# anaMoCo.net
KiCad netlist of a schematic drawn in EAGLE
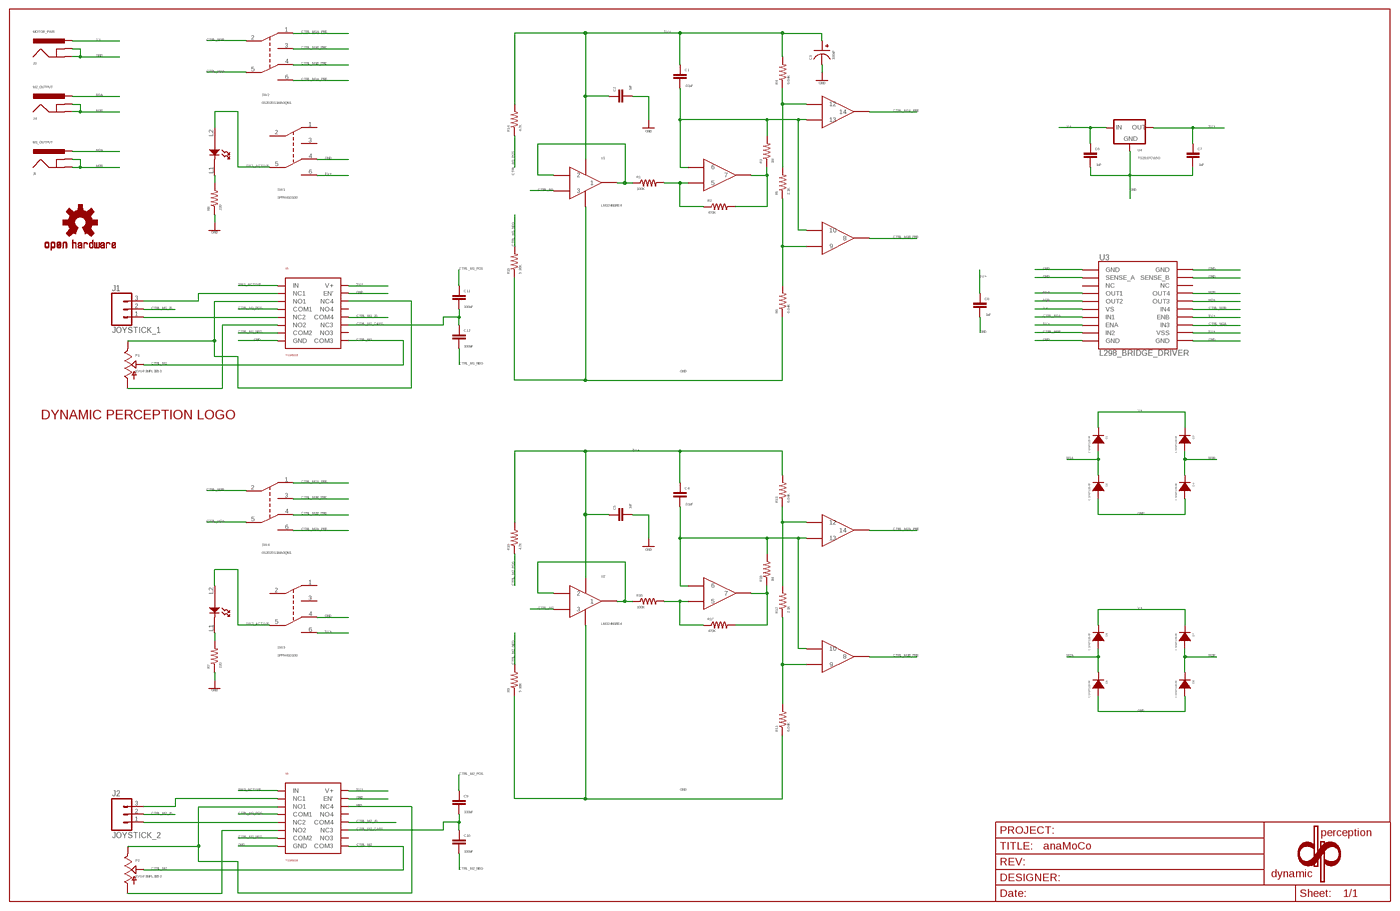
[diagram p0: schematic, sheet 1, overview]
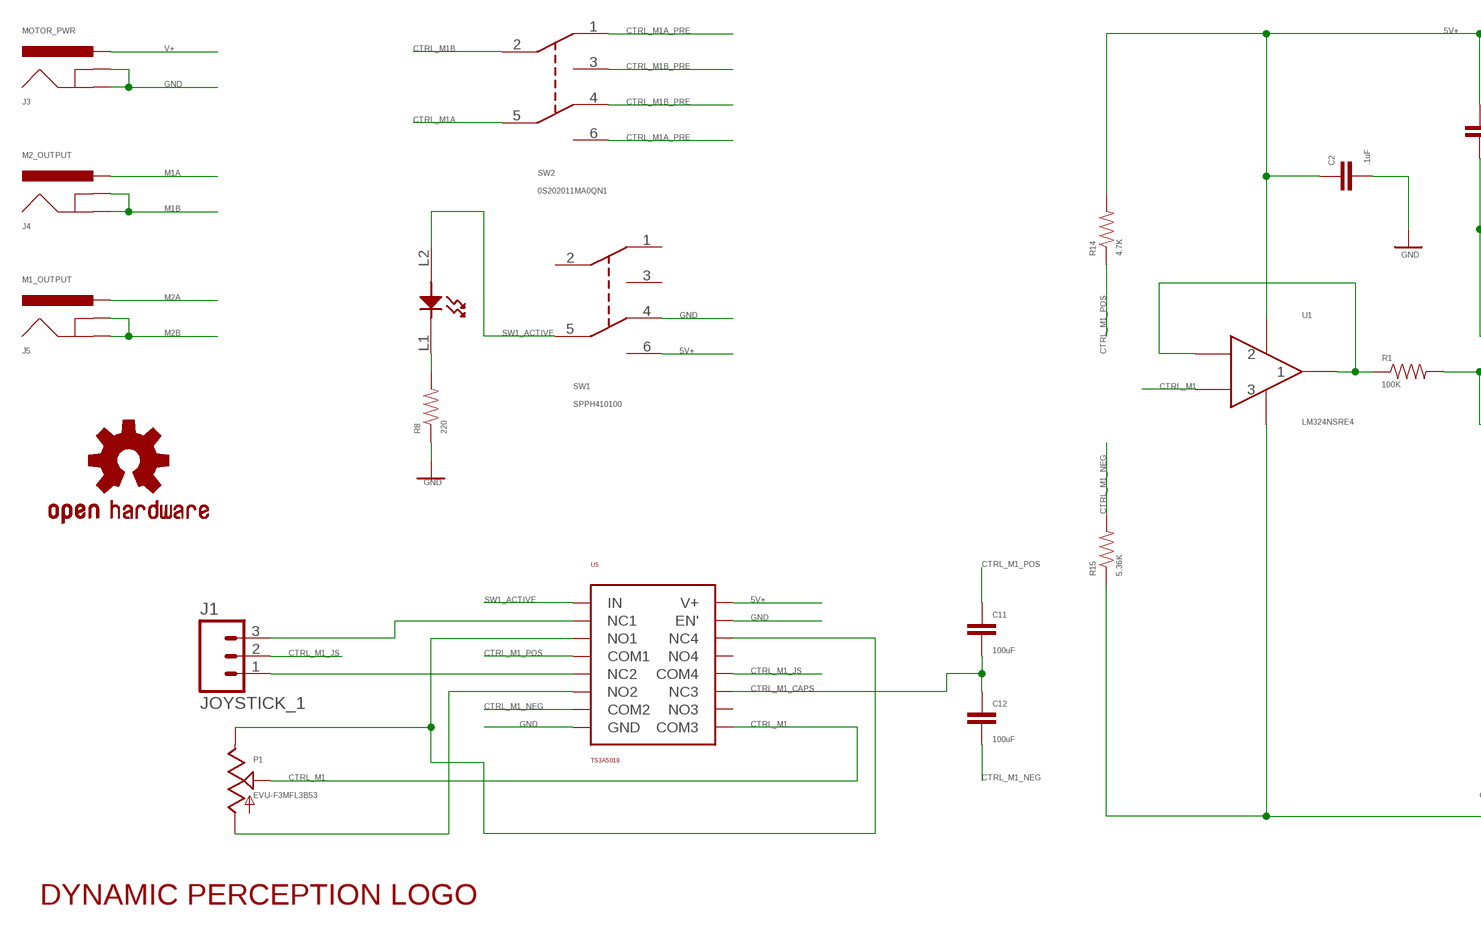
[diagram p1: schematic, sheet 1, part 1 of 4]
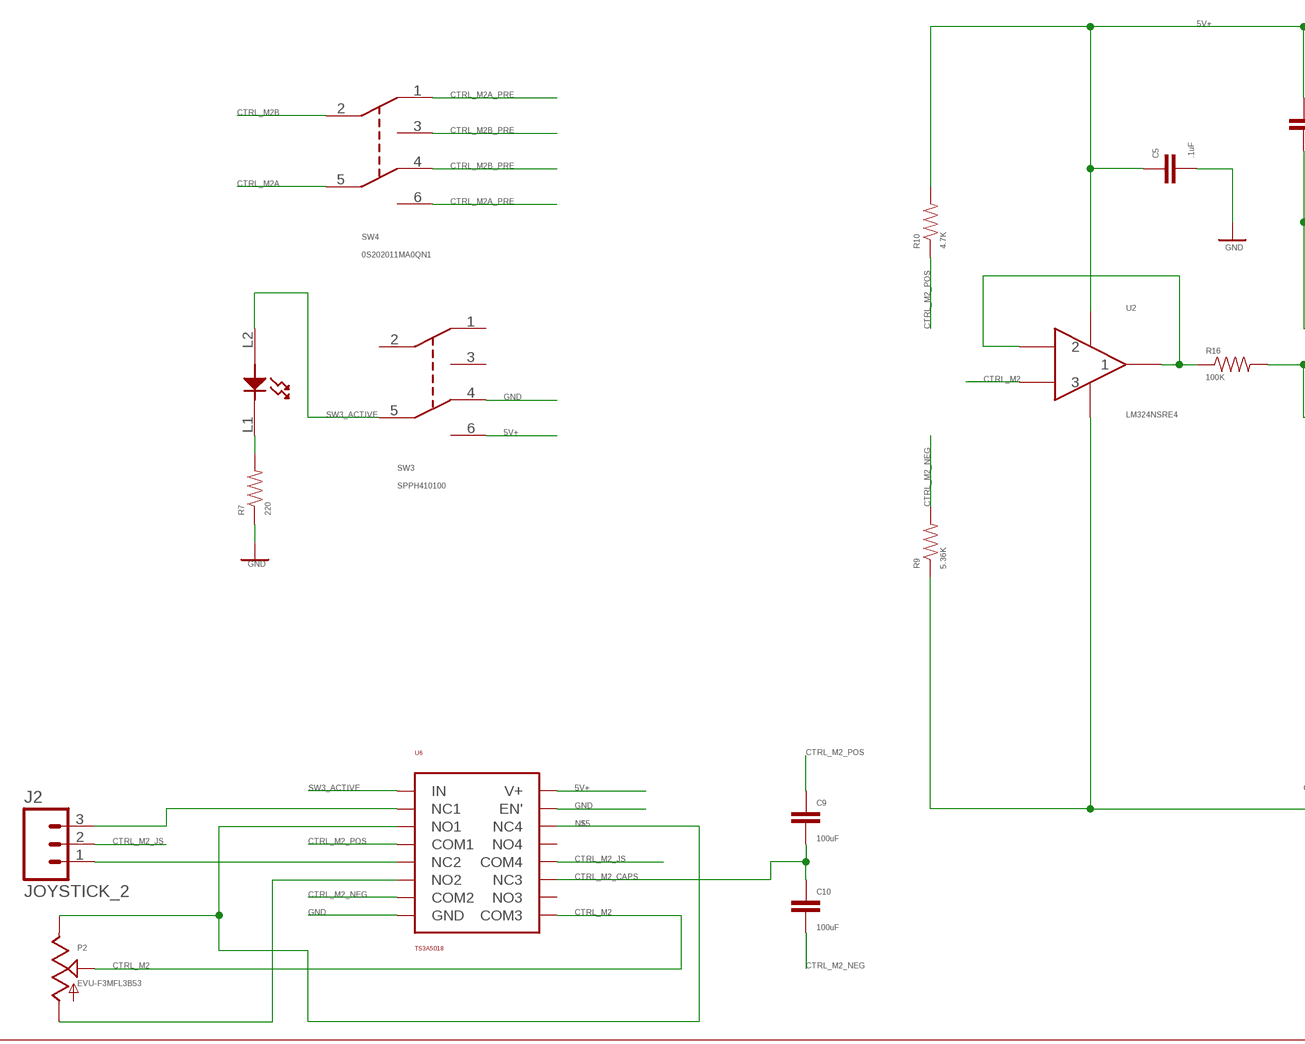
[diagram p2: schematic, sheet 1, part 2 of 4]
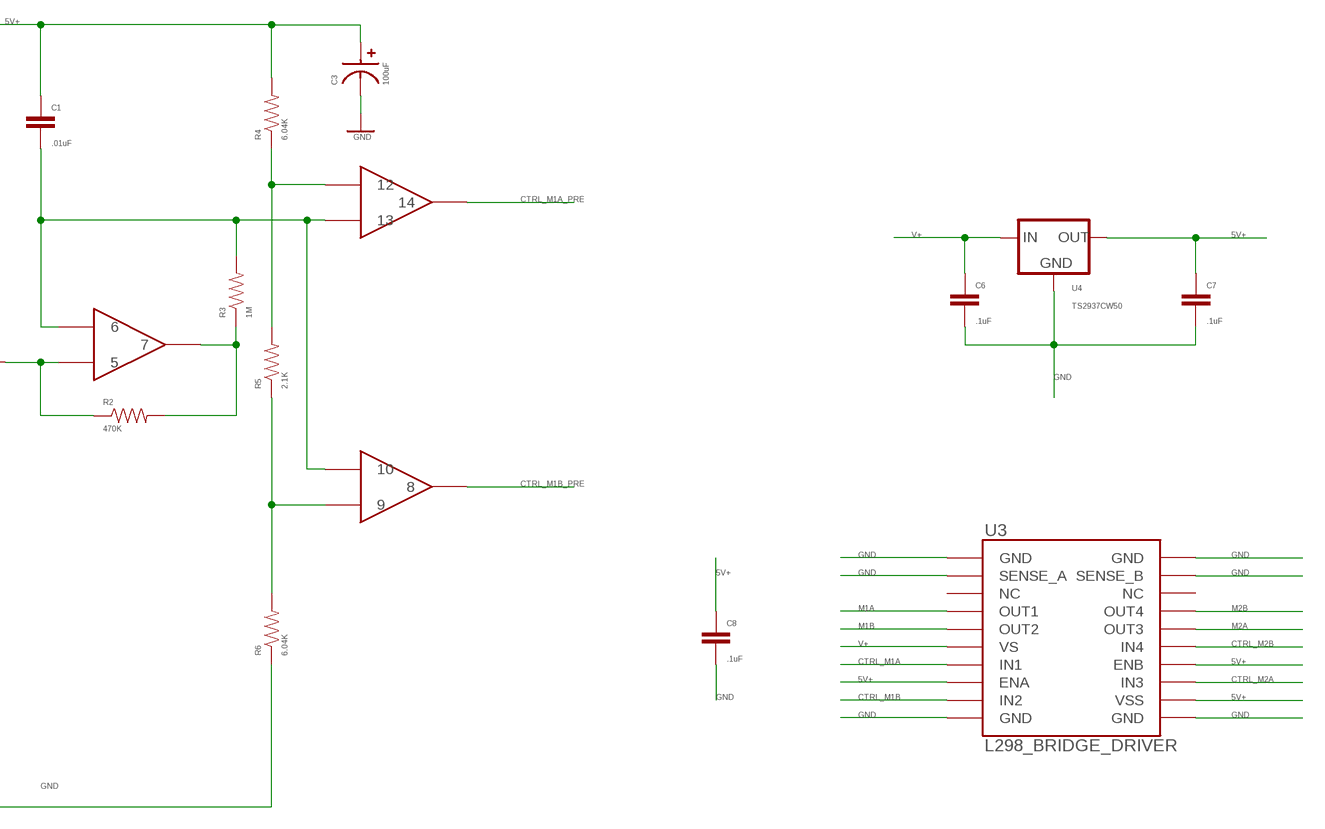
[diagram p3: schematic, sheet 1, part 3 of 4]
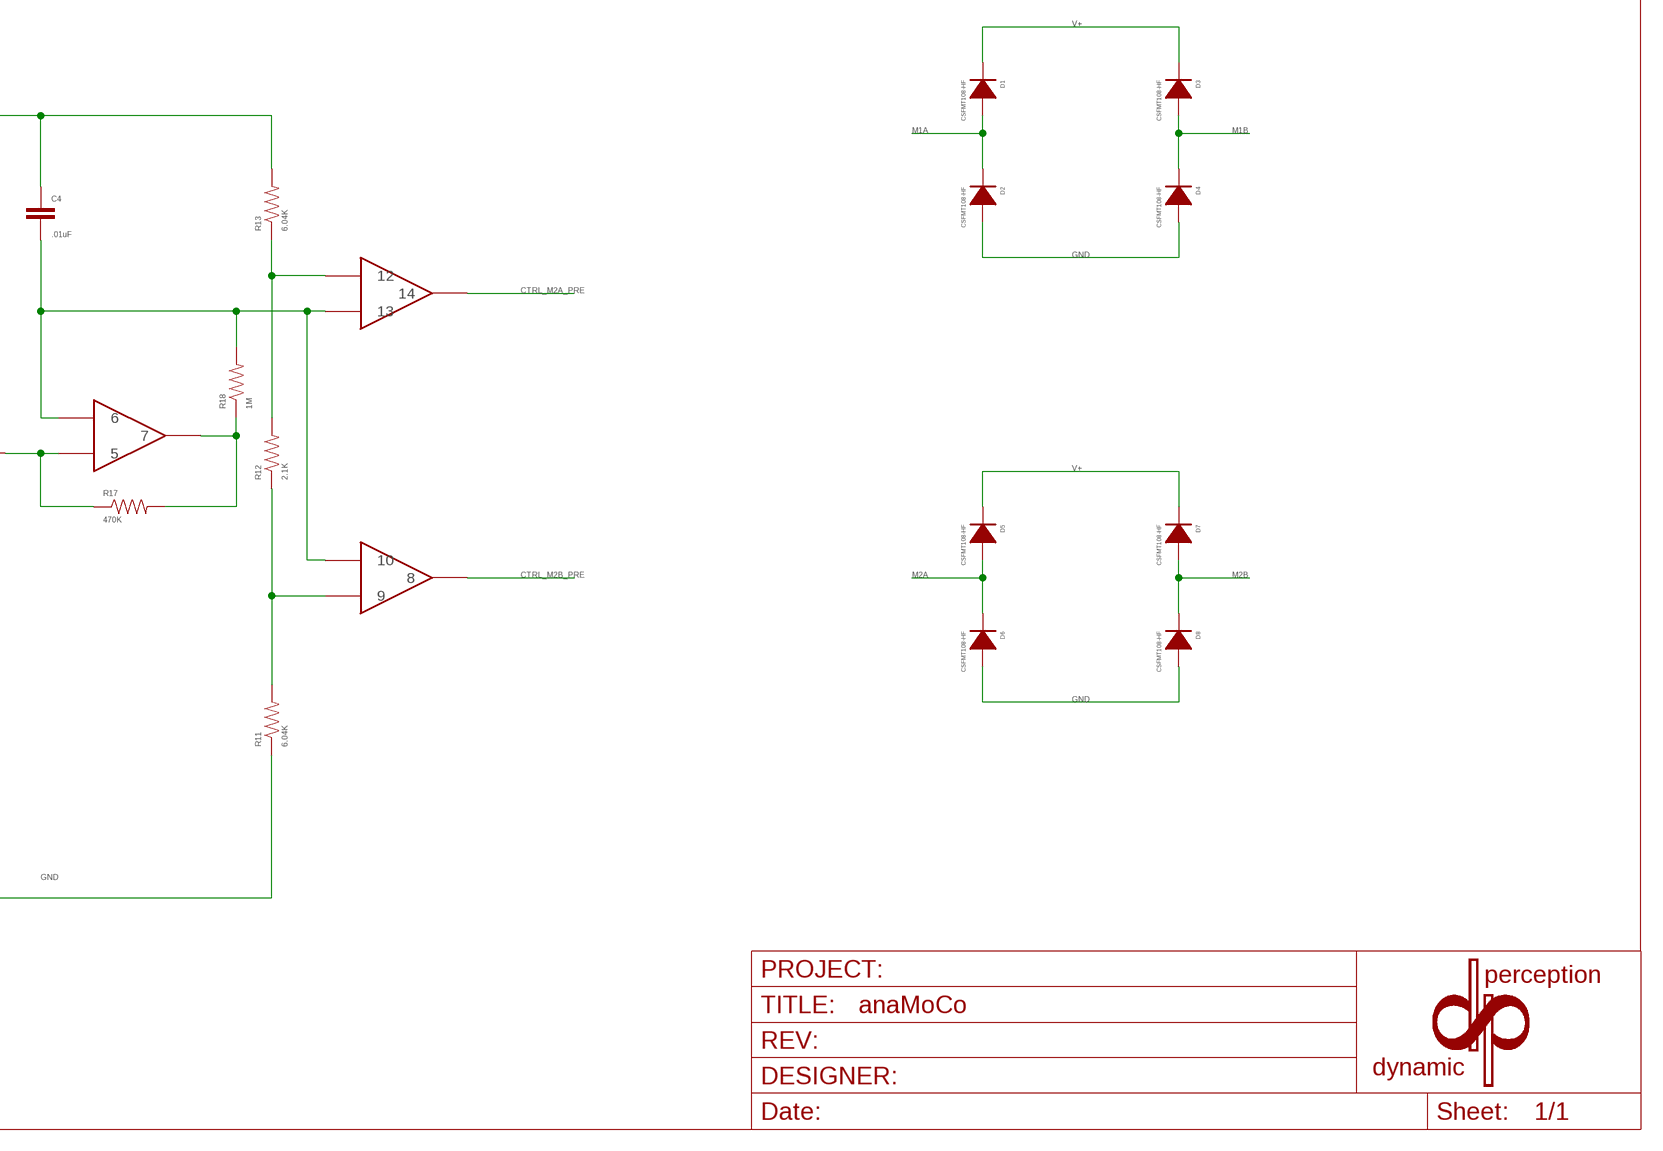
[diagram p4: schematic, sheet 1, part 4 of 4]

(export (version "E")
  (design (tool "Eeschema 10.0.6"))
  (components
    (comp (ref "C1")
      (value ".01uF")
      (footprint "eagle-import:0402_CAP")
      (libsource (lib "eagle-import") (part "CAP_NONPOL0402"))
    )
    (comp (ref "C2")
      (value ".1uF")
      (footprint "eagle-import:0402_CAP")
      (libsource (lib "eagle-import") (part "CAP_NONPOL0402"))
    )
    (comp (ref "C3")
      (value "100uF")
      (footprint "eagle-import:6.3MM_DIA_CAP_SMD")
      (libsource (lib "eagle-import") (part "CAP_POLARIZED6.3MM_SMD"))
    )
    (comp (ref "C4")
      (value ".01uF")
      (footprint "eagle-import:0402_CAP")
      (libsource (lib "eagle-import") (part "CAP_NONPOL0402"))
    )
    (comp (ref "C5")
      (value ".1uF")
      (footprint "eagle-import:0402_CAP")
      (libsource (lib "eagle-import") (part "CAP_NONPOL0402"))
    )
    (comp (ref "C6")
      (value ".1uF")
      (footprint "eagle-import:0402_CAP")
      (libsource (lib "eagle-import") (part "CAP_NONPOL0402"))
    )
    (comp (ref "C7")
      (value ".1uF")
      (footprint "eagle-import:0402_CAP")
      (libsource (lib "eagle-import") (part "CAP_NONPOL0402"))
    )
    (comp (ref "C8")
      (value ".1uF")
      (footprint "eagle-import:0402_CAP")
      (libsource (lib "eagle-import") (part "CAP_NONPOL0402"))
    )
    (comp (ref "C9")
      (value "100uF")
      (footprint "eagle-import:1206")
      (libsource (lib "eagle-import") (part "CAP1206"))
    )
    (comp (ref "C10")
      (value "100uF")
      (footprint "eagle-import:1206")
      (libsource (lib "eagle-import") (part "CAP1206"))
    )
    (comp (ref "C11")
      (value "100uF")
      (footprint "eagle-import:1206")
      (libsource (lib "eagle-import") (part "CAP1206"))
    )
    (comp (ref "C12")
      (value "100uF")
      (footprint "eagle-import:1206")
      (libsource (lib "eagle-import") (part "CAP1206"))
    )
    (comp (ref "D1")
      (value "CSFMT108-HF")
      (footprint "eagle-import:SOD-123")
      (libsource (lib "eagle-import") (part "1N4148WSOD-123"))
    )
    (comp (ref "D2")
      (value "CSFMT108-HF")
      (footprint "eagle-import:SOD-123")
      (libsource (lib "eagle-import") (part "1N4148WSOD-123"))
    )
    (comp (ref "D3")
      (value "CSFMT108-HF")
      (footprint "eagle-import:SOD-123")
      (libsource (lib "eagle-import") (part "1N4148WSOD-123"))
    )
    (comp (ref "D4")
      (value "CSFMT108-HF")
      (footprint "eagle-import:SOD-123")
      (libsource (lib "eagle-import") (part "1N4148WSOD-123"))
    )
    (comp (ref "D5")
      (value "CSFMT108-HF")
      (footprint "eagle-import:SOD-123")
      (libsource (lib "eagle-import") (part "1N4148WSOD-123"))
    )
    (comp (ref "D6")
      (value "CSFMT108-HF")
      (footprint "eagle-import:SOD-123")
      (libsource (lib "eagle-import") (part "1N4148WSOD-123"))
    )
    (comp (ref "D7")
      (value "CSFMT108-HF")
      (footprint "eagle-import:SOD-123")
      (libsource (lib "eagle-import") (part "1N4148WSOD-123"))
    )
    (comp (ref "D8")
      (value "CSFMT108-HF")
      (footprint "eagle-import:SOD-123")
      (libsource (lib "eagle-import") (part "1N4148WSOD-123"))
    )
    (comp (ref "J1")
      (value "JOYSTICK_1")
      (footprint "eagle-import:MOLEX-1X3")
      (libsource (lib "eagle-import") (part "M03POLAR"))
    )
    (comp (ref "J2")
      (value "JOYSTICK_2")
      (footprint "eagle-import:MOLEX-1X3")
      (libsource (lib "eagle-import") (part "M03POLAR"))
    )
    (comp (ref "J3")
      (value "MOTOR_PWR")
      (footprint "eagle-import:POWER_JACK_PTH")
      (libsource (lib "eagle-import") (part "POWER_JACKPTH"))
    )
    (comp (ref "J4")
      (value "M2_OUTPUT")
      (footprint "eagle-import:POWER_JACK_PTH")
      (libsource (lib "eagle-import") (part "POWER_JACKPTH"))
    )
    (comp (ref "J5")
      (value "M1_OUTPUT")
      (footprint "eagle-import:POWER_JACK_PTH")
      (libsource (lib "eagle-import") (part "POWER_JACKPTH"))
    )
    (comp (ref "LOGO1")
      (value "DP_LOGOLARGE")
      (footprint "eagle-import:DP_LOGO_LARGE")
      (libsource (lib "eagle-import") (part "DP_LOGOLARGE"))
    )
    (comp (ref "P1")
      (value "EVU-F3MFL3B53")
      (footprint "eagle-import:PTV09A-4_POT")
      (libsource (lib "eagle-import") (part "POTENTIOMETERPTV09A-4"))
    )
    (comp (ref "P2")
      (value "EVU-F3MFL3B53")
      (footprint "eagle-import:PTV09A-4_POT")
      (libsource (lib "eagle-import") (part "POTENTIOMETERPTV09A-4"))
    )
    (comp (ref "R1")
      (value "100K")
      (footprint "eagle-import:0402_RES")
      (libsource (lib "eagle-import") (part "RESISTOR0402"))
    )
    (comp (ref "R2")
      (value "470K")
      (footprint "eagle-import:0402_RES")
      (libsource (lib "eagle-import") (part "RESISTOR0402"))
    )
    (comp (ref "R3")
      (value "1M")
      (footprint "eagle-import:0402_RES")
      (libsource (lib "eagle-import") (part "RESISTOR0402"))
    )
    (comp (ref "R4")
      (value "6.04K")
      (footprint "eagle-import:0402_RES")
      (libsource (lib "eagle-import") (part "RESISTOR0402"))
    )
    (comp (ref "R5")
      (value "2.1K")
      (footprint "eagle-import:0402_RES")
      (libsource (lib "eagle-import") (part "RESISTOR0402"))
    )
    (comp (ref "R6")
      (value "6.04K")
      (footprint "eagle-import:0402_RES")
      (libsource (lib "eagle-import") (part "RESISTOR0402"))
    )
    (comp (ref "R7")
      (value "220")
      (footprint "eagle-import:0402_RES")
      (libsource (lib "eagle-import") (part "RESISTOR0402"))
    )
    (comp (ref "R8")
      (value "220")
      (footprint "eagle-import:0402_RES")
      (libsource (lib "eagle-import") (part "RESISTOR0402"))
    )
    (comp (ref "R9")
      (value "5.36K")
      (footprint "eagle-import:0402_RES")
      (libsource (lib "eagle-import") (part "RESISTOR0402"))
    )
    (comp (ref "R10")
      (value "4.7K")
      (footprint "eagle-import:0402_RES")
      (libsource (lib "eagle-import") (part "RESISTOR0402"))
    )
    (comp (ref "R11")
      (value "6.04K")
      (footprint "eagle-import:0402_RES")
      (libsource (lib "eagle-import") (part "RESISTOR0402"))
    )
    (comp (ref "R12")
      (value "2.1K")
      (footprint "eagle-import:0402_RES")
      (libsource (lib "eagle-import") (part "RESISTOR0402"))
    )
    (comp (ref "R13")
      (value "6.04K")
      (footprint "eagle-import:0402_RES")
      (libsource (lib "eagle-import") (part "RESISTOR0402"))
    )
    (comp (ref "R14")
      (value "4.7K")
      (footprint "eagle-import:0402_RES")
      (libsource (lib "eagle-import") (part "RESISTOR0402"))
    )
    (comp (ref "R15")
      (value "5.36K")
      (footprint "eagle-import:0402_RES")
      (libsource (lib "eagle-import") (part "RESISTOR0402"))
    )
    (comp (ref "R16")
      (value "100K")
      (footprint "eagle-import:0402_RES")
      (libsource (lib "eagle-import") (part "RESISTOR0402"))
    )
    (comp (ref "R17")
      (value "470K")
      (footprint "eagle-import:0402_RES")
      (libsource (lib "eagle-import") (part "RESISTOR0402"))
    )
    (comp (ref "R18")
      (value "1M")
      (footprint "eagle-import:0402_RES")
      (libsource (lib "eagle-import") (part "RESISTOR0402"))
    )
    (comp (ref "SW1")
      (value "SPPH410100")
      (footprint "eagle-import:PS004_SW")
      (libsource (lib "eagle-import") (part "PS004_SWPS004"))
    )
    (comp (ref "SW2")
      (value "0S202011MA0QN1")
      (footprint "eagle-import:OS202011MA0QN1")
      (libsource (lib "eagle-import") (part "DPDTOS202011MA0QN1"))
    )
    (comp (ref "SW3")
      (value "SPPH410100")
      (footprint "eagle-import:PS004_SW")
      (libsource (lib "eagle-import") (part "PS004_SWPS004"))
    )
    (comp (ref "SW4")
      (value "0S202011MA0QN1")
      (footprint "eagle-import:OS202011MA0QN1")
      (libsource (lib "eagle-import") (part "DPDTOS202011MA0QN1"))
    )
    (comp (ref "U$1")
      (value "OSHW-LOGOM")
      (footprint "eagle-import:OSHW-LOGO-M")
      (libsource (lib "eagle-import") (part "OSHW-LOGOM"))
    )
    (comp (ref "U$2")
      (value "DP_FRAME")
      (footprint "eagle-import:DP_FRAME")
      (fields
        (field (name "DNAME") "PARKER DILLMANN")
        (field (name "PNAME") "anaMoCo")
        (field (name "REVNUM") "7")
      )
      (libsource (lib "eagle-import") (part "DP_FRAME"))
    )
    (comp (ref "U1")
      (value "LM324NSRE4")
      (footprint "eagle-import:SOP-14")
      (libsource (lib "eagle-import") (part "LM324SOP-14"))
    )
    (comp (ref "U2")
      (value "LM324NSRE4")
      (footprint "eagle-import:SOP-14")
      (libsource (lib "eagle-import") (part "LM324SOP-14"))
    )
    (comp (ref "U3")
      (value "L298_BRIDGE_DRIVER")
      (footprint "eagle-import:POWERSO20")
      (libsource (lib "eagle-import") (part "L298_BRIDGE_DRIVER"))
    )
    (comp (ref "U4")
      (value "TS2937CW50")
      (footprint "eagle-import:SOT223")
      (libsource (lib "eagle-import") (part "V_REG_MIC2920"))
    )
    (comp (ref "U5")
      (value "TS3A5018")
      (footprint "eagle-import:TTSOP-16")
      (libsource (lib "eagle-import") (part "TS3A5018TTSOP-16"))
    )
    (comp (ref "U6")
      (value "TS3A5018")
      (footprint "eagle-import:TTSOP-16")
      (libsource (lib "eagle-import") (part "TS3A5018TTSOP-16"))
    )
  )
  (nets
    (net (code "1") (name "/5V+") (class "Default")
      (node (ref "C1") (pin "1") (pinfunction "1_1") (pintype "passive"))
      (node (ref "C2") (pin "1") (pinfunction "1_1") (pintype "passive"))
      (node (ref "C3") (pin "POS") (pinfunction "POS_POS") (pintype "bidirectional"))
      (node (ref "C4") (pin "1") (pinfunction "1_1") (pintype "passive"))
      (node (ref "C5") (pin "1") (pinfunction "1_1") (pintype "passive"))
      (node (ref "C7") (pin "1") (pinfunction "1_1") (pintype "passive"))
      (node (ref "C8") (pin "1") (pinfunction "1_1") (pintype "passive"))
      (node (ref "R10") (pin "2") (pinfunction "2_2") (pintype "passive"))
      (node (ref "R13") (pin "2") (pinfunction "2_2") (pintype "passive"))
      (node (ref "R14") (pin "2") (pinfunction "2_2") (pintype "passive"))
      (node (ref "R4") (pin "2") (pinfunction "2_2") (pintype "passive"))
      (node (ref "SW1") (pin "6") (pinfunction "6_6") (pintype "bidirectional"))
      (node (ref "SW3") (pin "6") (pinfunction "6_6") (pintype "bidirectional"))
      (node (ref "U1") (pin "4") (pinfunction "4_4") (pintype "bidirectional"))
      (node (ref "U2") (pin "4") (pinfunction "4_4") (pintype "bidirectional"))
      (node (ref "U3") (pin "12") (pinfunction "VSS_12") (pintype "bidirectional"))
      (node (ref "U3") (pin "14") (pinfunction "ENB_14") (pintype "bidirectional"))
      (node (ref "U3") (pin "8") (pinfunction "ENA_8") (pintype "bidirectional"))
      (node (ref "U4") (pin "3") (pinfunction "OUT_3") (pintype "output"))
      (node (ref "U5") (pin "16") (pinfunction "V+_16") (pintype "bidirectional"))
      (node (ref "U6") (pin "16") (pinfunction "V+_16") (pintype "bidirectional"))
    )
    (net (code "2") (name "/CTRL_M1") (class "Default")
      (node (ref "P1") (pin "2") (pinfunction "2_2") (pintype "bidirectional"))
      (node (ref "U1") (pin "3") (pinfunction "3_3") (pintype "bidirectional"))
      (node (ref "U5") (pin "9") (pinfunction "COM3_9") (pintype "bidirectional"))
    )
    (net (code "3") (name "/CTRL_M1A") (class "Default")
      (node (ref "SW2") (pin "5") (pinfunction "5_5") (pintype "bidirectional"))
      (node (ref "U3") (pin "7") (pinfunction "IN1_7") (pintype "bidirectional"))
    )
    (net (code "4") (name "/CTRL_M1A_PRE") (class "Default")
      (node (ref "SW2") (pin "1") (pinfunction "1_1") (pintype "bidirectional"))
      (node (ref "SW2") (pin "6") (pinfunction "6_6") (pintype "bidirectional"))
      (node (ref "U1") (pin "14") (pinfunction "14_14") (pintype "bidirectional"))
    )
    (net (code "5") (name "/CTRL_M1B") (class "Default")
      (node (ref "SW2") (pin "2") (pinfunction "2_2") (pintype "bidirectional"))
      (node (ref "U3") (pin "9") (pinfunction "IN2_9") (pintype "bidirectional"))
    )
    (net (code "6") (name "/CTRL_M1B_PRE") (class "Default")
      (node (ref "SW2") (pin "3") (pinfunction "3_3") (pintype "bidirectional"))
      (node (ref "SW2") (pin "4") (pinfunction "4_4") (pintype "bidirectional"))
      (node (ref "U1") (pin "8") (pinfunction "8_8") (pintype "bidirectional"))
    )
    (net (code "7") (name "/CTRL_M1_CAPS") (class "Default")
      (node (ref "C11") (pin "2") (pinfunction "2_2") (pintype "passive"))
      (node (ref "C12") (pin "1") (pinfunction "1_1") (pintype "passive"))
      (node (ref "U5") (pin "11") (pinfunction "NC3_11") (pintype "bidirectional"))
    )
    (net (code "8") (name "/CTRL_M1_JS") (class "Default")
      (node (ref "J1") (pin "2") (pinfunction "2_2") (pintype "passive"))
      (node (ref "U5") (pin "12") (pinfunction "COM4_12") (pintype "bidirectional"))
    )
    (net (code "9") (name "/CTRL_M1_NEG") (class "Default")
      (node (ref "C12") (pin "2") (pinfunction "2_2") (pintype "passive"))
      (node (ref "R15") (pin "2") (pinfunction "2_2") (pintype "passive"))
      (node (ref "U5") (pin "7") (pinfunction "COM2_7") (pintype "bidirectional"))
    )
    (net (code "10") (name "/CTRL_M1_POS") (class "Default")
      (node (ref "C11") (pin "1") (pinfunction "1_1") (pintype "passive"))
      (node (ref "R14") (pin "1") (pinfunction "1_1") (pintype "passive"))
      (node (ref "U5") (pin "4") (pinfunction "COM1_4") (pintype "bidirectional"))
    )
    (net (code "11") (name "/CTRL_M2") (class "Default")
      (node (ref "P2") (pin "2") (pinfunction "2_2") (pintype "bidirectional"))
      (node (ref "U2") (pin "3") (pinfunction "3_3") (pintype "bidirectional"))
      (node (ref "U6") (pin "9") (pinfunction "COM3_9") (pintype "bidirectional"))
    )
    (net (code "12") (name "/CTRL_M2A") (class "Default")
      (node (ref "SW4") (pin "5") (pinfunction "5_5") (pintype "bidirectional"))
      (node (ref "U3") (pin "13") (pinfunction "IN3_13") (pintype "bidirectional"))
    )
    (net (code "13") (name "/CTRL_M2A_PRE") (class "Default")
      (node (ref "SW4") (pin "1") (pinfunction "1_1") (pintype "bidirectional"))
      (node (ref "SW4") (pin "6") (pinfunction "6_6") (pintype "bidirectional"))
      (node (ref "U2") (pin "14") (pinfunction "14_14") (pintype "bidirectional"))
    )
    (net (code "14") (name "/CTRL_M2B") (class "Default")
      (node (ref "SW4") (pin "2") (pinfunction "2_2") (pintype "bidirectional"))
      (node (ref "U3") (pin "15") (pinfunction "IN4_15") (pintype "bidirectional"))
    )
    (net (code "15") (name "/CTRL_M2B_PRE") (class "Default")
      (node (ref "SW4") (pin "3") (pinfunction "3_3") (pintype "bidirectional"))
      (node (ref "SW4") (pin "4") (pinfunction "4_4") (pintype "bidirectional"))
      (node (ref "U2") (pin "8") (pinfunction "8_8") (pintype "bidirectional"))
    )
    (net (code "16") (name "/CTRL_M2_CAPS") (class "Default")
      (node (ref "C10") (pin "1") (pinfunction "1_1") (pintype "passive"))
      (node (ref "C9") (pin "2") (pinfunction "2_2") (pintype "passive"))
      (node (ref "U6") (pin "11") (pinfunction "NC3_11") (pintype "bidirectional"))
    )
    (net (code "17") (name "/CTRL_M2_JS") (class "Default")
      (node (ref "J2") (pin "2") (pinfunction "2_2") (pintype "passive"))
      (node (ref "U6") (pin "12") (pinfunction "COM4_12") (pintype "bidirectional"))
    )
    (net (code "18") (name "/CTRL_M2_NEG") (class "Default")
      (node (ref "C10") (pin "2") (pinfunction "2_2") (pintype "passive"))
      (node (ref "R9") (pin "2") (pinfunction "2_2") (pintype "passive"))
      (node (ref "U6") (pin "7") (pinfunction "COM2_7") (pintype "bidirectional"))
    )
    (net (code "19") (name "/CTRL_M2_POS") (class "Default")
      (node (ref "C9") (pin "1") (pinfunction "1_1") (pintype "passive"))
      (node (ref "R10") (pin "1") (pinfunction "1_1") (pintype "passive"))
      (node (ref "U6") (pin "4") (pinfunction "COM1_4") (pintype "bidirectional"))
    )
    (net (code "20") (name "/M1A") (class "Default")
      (node (ref "D1") (pin "ANODE") (pinfunction "ANODE_ANODE") (pintype "bidirectional"))
      (node (ref "D2") (pin "CATHODE") (pinfunction "CATHODE_CATHODE") (pintype "bidirectional"))
      (node (ref "J4") (pin "PWR") (pinfunction "PWR_PWR") (pintype "bidirectional"))
      (node (ref "U3") (pin "4") (pinfunction "OUT1_4") (pintype "bidirectional"))
    )
    (net (code "21") (name "/M1B") (class "Default")
      (node (ref "D3") (pin "ANODE") (pinfunction "ANODE_ANODE") (pintype "bidirectional"))
      (node (ref "D4") (pin "CATHODE") (pinfunction "CATHODE_CATHODE") (pintype "bidirectional"))
      (node (ref "J4") (pin "GND") (pinfunction "GND_GND") (pintype "bidirectional"))
      (node (ref "J4") (pin "GNDBREAK") (pinfunction "GNDBREAK_GNDBREAK") (pintype "bidirectional"))
      (node (ref "U3") (pin "5") (pinfunction "OUT2_5") (pintype "bidirectional"))
    )
    (net (code "22") (name "/M2A") (class "Default")
      (node (ref "D5") (pin "ANODE") (pinfunction "ANODE_ANODE") (pintype "bidirectional"))
      (node (ref "D6") (pin "CATHODE") (pinfunction "CATHODE_CATHODE") (pintype "bidirectional"))
      (node (ref "J5") (pin "PWR") (pinfunction "PWR_PWR") (pintype "bidirectional"))
      (node (ref "U3") (pin "16") (pinfunction "OUT3_16") (pintype "bidirectional"))
    )
    (net (code "23") (name "/M2B") (class "Default")
      (node (ref "D7") (pin "ANODE") (pinfunction "ANODE_ANODE") (pintype "bidirectional"))
      (node (ref "D8") (pin "CATHODE") (pinfunction "CATHODE_CATHODE") (pintype "bidirectional"))
      (node (ref "J5") (pin "GND") (pinfunction "GND_GND") (pintype "bidirectional"))
      (node (ref "J5") (pin "GNDBREAK") (pinfunction "GNDBREAK_GNDBREAK") (pintype "bidirectional"))
      (node (ref "U3") (pin "17") (pinfunction "OUT4_17") (pintype "bidirectional"))
    )
    (net (code "24") (name "/N$5") (class "Default")
      (node (ref "P2") (pin "1") (pinfunction "1_1") (pintype "bidirectional"))
      (node (ref "U6") (pin "14") (pinfunction "NC4_14") (pintype "bidirectional"))
      (node (ref "U6") (pin "3") (pinfunction "NO1_3") (pintype "bidirectional"))
    )
    (net (code "25") (name "/SW1_ACTIVE") (class "Default")
      (node (ref "SW1") (pin "5") (pinfunction "5_5") (pintype "bidirectional"))
      (node (ref "SW1") (pin "L2") (pinfunction "L1_L2") (pintype "bidirectional"))
      (node (ref "U5") (pin "1") (pinfunction "IN_1") (pintype "bidirectional"))
    )
    (net (code "26") (name "/SW3_ACTIVE") (class "Default")
      (node (ref "SW3") (pin "5") (pinfunction "5_5") (pintype "bidirectional"))
      (node (ref "SW3") (pin "L2") (pinfunction "L1_L2") (pintype "bidirectional"))
      (node (ref "U6") (pin "1") (pinfunction "IN_1") (pintype "bidirectional"))
    )
    (net (code "27") (name "/V+") (class "Default")
      (node (ref "C6") (pin "1") (pinfunction "1_1") (pintype "passive"))
      (node (ref "D1") (pin "CATHODE") (pinfunction "CATHODE_CATHODE") (pintype "bidirectional"))
      (node (ref "D3") (pin "CATHODE") (pinfunction "CATHODE_CATHODE") (pintype "bidirectional"))
      (node (ref "D5") (pin "CATHODE") (pinfunction "CATHODE_CATHODE") (pintype "bidirectional"))
      (node (ref "D7") (pin "CATHODE") (pinfunction "CATHODE_CATHODE") (pintype "bidirectional"))
      (node (ref "J3") (pin "PWR") (pinfunction "PWR_PWR") (pintype "bidirectional"))
      (node (ref "U3") (pin "6") (pinfunction "VS_6") (pintype "bidirectional"))
      (node (ref "U4") (pin "1") (pinfunction "IN_1") (pintype "input"))
    )
    (net (code "28") (name "GND") (class "Default")
      (node (ref "C2") (pin "2") (pinfunction "2_2") (pintype "passive"))
      (node (ref "C3") (pin "NEG") (pinfunction "NEG_NEG") (pintype "bidirectional"))
      (node (ref "C5") (pin "2") (pinfunction "2_2") (pintype "passive"))
      (node (ref "C6") (pin "2") (pinfunction "2_2") (pintype "passive"))
      (node (ref "C7") (pin "2") (pinfunction "2_2") (pintype "passive"))
      (node (ref "C8") (pin "2") (pinfunction "2_2") (pintype "passive"))
      (node (ref "D2") (pin "ANODE") (pinfunction "ANODE_ANODE") (pintype "bidirectional"))
      (node (ref "D4") (pin "ANODE") (pinfunction "ANODE_ANODE") (pintype "bidirectional"))
      (node (ref "D6") (pin "ANODE") (pinfunction "ANODE_ANODE") (pintype "bidirectional"))
      (node (ref "D8") (pin "ANODE") (pinfunction "ANODE_ANODE") (pintype "bidirectional"))
      (node (ref "J3") (pin "GND") (pinfunction "GND_GND") (pintype "bidirectional"))
      (node (ref "J3") (pin "GNDBREAK") (pinfunction "GNDBREAK_GNDBREAK") (pintype "bidirectional"))
      (node (ref "R11") (pin "1") (pinfunction "1_1") (pintype "passive"))
      (node (ref "R15") (pin "1") (pinfunction "1_1") (pintype "passive"))
      (node (ref "R6") (pin "1") (pinfunction "1_1") (pintype "passive"))
      (node (ref "R7") (pin "1") (pinfunction "1_1") (pintype "passive"))
      (node (ref "R8") (pin "1") (pinfunction "1_1") (pintype "passive"))
      (node (ref "R9") (pin "1") (pinfunction "1_1") (pintype "passive"))
      (node (ref "SW1") (pin "4") (pinfunction "4_4") (pintype "bidirectional"))
      (node (ref "SW3") (pin "4") (pinfunction "4_4") (pintype "bidirectional"))
      (node (ref "U1") (pin "11") (pinfunction "11_11") (pintype "bidirectional"))
      (node (ref "U2") (pin "11") (pinfunction "11_11") (pintype "bidirectional"))
      (node (ref "U3") (pin "1") (pinfunction "GND_1") (pintype "bidirectional"))
      (node (ref "U3") (pin "10") (pinfunction "GND_10") (pintype "bidirectional"))
      (node (ref "U3") (pin "11") (pinfunction "GND_11") (pintype "bidirectional"))
      (node (ref "U3") (pin "19") (pinfunction "SENSE_B_19") (pintype "bidirectional"))
      (node (ref "U3") (pin "2") (pinfunction "SENSE_A_2") (pintype "bidirectional"))
      (node (ref "U3") (pin "20") (pinfunction "GND_20") (pintype "bidirectional"))
      (node (ref "U4") (pin "2") (pinfunction "GND_2") (pintype "input"))
      (node (ref "U5") (pin "15") (pinfunction "EN'_15") (pintype "bidirectional"))
      (node (ref "U5") (pin "8") (pinfunction "GND_8") (pintype "bidirectional"))
      (node (ref "U6") (pin "15") (pinfunction "EN'_15") (pintype "bidirectional"))
      (node (ref "U6") (pin "8") (pinfunction "GND_8") (pintype "bidirectional"))
    )
    (net (code "29") (name "Net-(C1-Pad2)") (class "Default")
      (node (ref "C1") (pin "2") (pinfunction "2_2") (pintype "passive"))
      (node (ref "R3") (pin "2") (pinfunction "2_2") (pintype "passive"))
      (node (ref "U1") (pin "10") (pinfunction "10_10") (pintype "bidirectional"))
      (node (ref "U1") (pin "13") (pinfunction "13_13") (pintype "bidirectional"))
      (node (ref "U1") (pin "6") (pinfunction "6_6") (pintype "bidirectional"))
    )
    (net (code "30") (name "Net-(C4-Pad2)") (class "Default")
      (node (ref "C4") (pin "2") (pinfunction "2_2") (pintype "passive"))
      (node (ref "R18") (pin "2") (pinfunction "2_2") (pintype "passive"))
      (node (ref "U2") (pin "10") (pinfunction "10_10") (pintype "bidirectional"))
      (node (ref "U2") (pin "13") (pinfunction "13_13") (pintype "bidirectional"))
      (node (ref "U2") (pin "6") (pinfunction "6_6") (pintype "bidirectional"))
    )
    (net (code "31") (name "Net-(R1-Pad1)") (class "Default")
      (node (ref "R1") (pin "1") (pinfunction "1_1") (pintype "passive"))
      (node (ref "U1") (pin "1") (pinfunction "1_1") (pintype "bidirectional"))
      (node (ref "U1") (pin "2") (pinfunction "2_2") (pintype "bidirectional"))
    )
    (net (code "32") (name "Net-(R1-Pad2)") (class "Default")
      (node (ref "R1") (pin "2") (pinfunction "2_2") (pintype "passive"))
      (node (ref "R2") (pin "1") (pinfunction "1_1") (pintype "passive"))
      (node (ref "U1") (pin "5") (pinfunction "5_5") (pintype "bidirectional"))
    )
    (net (code "33") (name "Net-(R2-Pad2)") (class "Default")
      (node (ref "R2") (pin "2") (pinfunction "2_2") (pintype "passive"))
      (node (ref "R3") (pin "1") (pinfunction "1_1") (pintype "passive"))
      (node (ref "U1") (pin "7") (pinfunction "7_7") (pintype "bidirectional"))
    )
    (net (code "34") (name "Net-(R4-Pad1)") (class "Default")
      (node (ref "R4") (pin "1") (pinfunction "1_1") (pintype "passive"))
      (node (ref "R5") (pin "2") (pinfunction "2_2") (pintype "passive"))
      (node (ref "U1") (pin "12") (pinfunction "12_12") (pintype "bidirectional"))
    )
    (net (code "35") (name "Net-(R5-Pad1)") (class "Default")
      (node (ref "R5") (pin "1") (pinfunction "1_1") (pintype "passive"))
      (node (ref "R6") (pin "2") (pinfunction "2_2") (pintype "passive"))
      (node (ref "U1") (pin "9") (pinfunction "9_9") (pintype "bidirectional"))
    )
    (net (code "36") (name "Net-(R11-Pad2)") (class "Default")
      (node (ref "R11") (pin "2") (pinfunction "2_2") (pintype "passive"))
      (node (ref "R12") (pin "1") (pinfunction "1_1") (pintype "passive"))
      (node (ref "U2") (pin "9") (pinfunction "9_9") (pintype "bidirectional"))
    )
    (net (code "37") (name "Net-(R12-Pad2)") (class "Default")
      (node (ref "R12") (pin "2") (pinfunction "2_2") (pintype "passive"))
      (node (ref "R13") (pin "1") (pinfunction "1_1") (pintype "passive"))
      (node (ref "U2") (pin "12") (pinfunction "12_12") (pintype "bidirectional"))
    )
    (net (code "38") (name "Net-(R16-Pad1)") (class "Default")
      (node (ref "R16") (pin "1") (pinfunction "1_1") (pintype "passive"))
      (node (ref "U2") (pin "1") (pinfunction "1_1") (pintype "bidirectional"))
      (node (ref "U2") (pin "2") (pinfunction "2_2") (pintype "bidirectional"))
    )
    (net (code "39") (name "Net-(R16-Pad2)") (class "Default")
      (node (ref "R16") (pin "2") (pinfunction "2_2") (pintype "passive"))
      (node (ref "R17") (pin "1") (pinfunction "1_1") (pintype "passive"))
      (node (ref "U2") (pin "5") (pinfunction "5_5") (pintype "bidirectional"))
    )
    (net (code "40") (name "Net-(R17-Pad2)") (class "Default")
      (node (ref "R17") (pin "2") (pinfunction "2_2") (pintype "passive"))
      (node (ref "R18") (pin "1") (pinfunction "1_1") (pintype "passive"))
      (node (ref "U2") (pin "7") (pinfunction "7_7") (pintype "bidirectional"))
    )
    (net (code "41") (name "Net-(SW1-L2)") (class "Default")
      (node (ref "R8") (pin "2") (pinfunction "2_2") (pintype "passive"))
      (node (ref "SW1") (pin "L1") (pinfunction "L2_L1") (pintype "bidirectional"))
    )
    (net (code "42") (name "Net-(SW3-L2)") (class "Default")
      (node (ref "R7") (pin "2") (pinfunction "2_2") (pintype "passive"))
      (node (ref "SW3") (pin "L1") (pinfunction "L2_L1") (pintype "bidirectional"))
    )
    (net (code "43") (name "Net-(U5-NC1)") (class "Default")
      (node (ref "J1") (pin "3") (pinfunction "3_3") (pintype "passive"))
      (node (ref "U5") (pin "2") (pinfunction "NC1_2") (pintype "bidirectional"))
    )
    (net (code "44") (name "Net-(U5-NC2)") (class "Default")
      (node (ref "J1") (pin "1") (pinfunction "1_1") (pintype "passive"))
      (node (ref "U5") (pin "5") (pinfunction "NC2_5") (pintype "bidirectional"))
    )
    (net (code "45") (name "Net-(U5-NC4)") (class "Default")
      (node (ref "P1") (pin "1") (pinfunction "1_1") (pintype "bidirectional"))
      (node (ref "U5") (pin "14") (pinfunction "NC4_14") (pintype "bidirectional"))
      (node (ref "U5") (pin "3") (pinfunction "NO1_3") (pintype "bidirectional"))
    )
    (net (code "46") (name "Net-(U5-NO2)") (class "Default")
      (node (ref "P1") (pin "3") (pinfunction "3_3") (pintype "bidirectional"))
      (node (ref "U5") (pin "6") (pinfunction "NO2_6") (pintype "bidirectional"))
    )
    (net (code "47") (name "Net-(U6-NC1)") (class "Default")
      (node (ref "J2") (pin "3") (pinfunction "3_3") (pintype "passive"))
      (node (ref "U6") (pin "2") (pinfunction "NC1_2") (pintype "bidirectional"))
    )
    (net (code "48") (name "Net-(U6-NC2)") (class "Default")
      (node (ref "J2") (pin "1") (pinfunction "1_1") (pintype "passive"))
      (node (ref "U6") (pin "5") (pinfunction "NC2_5") (pintype "bidirectional"))
    )
    (net (code "49") (name "Net-(U6-NO2)") (class "Default")
      (node (ref "P2") (pin "3") (pinfunction "3_3") (pintype "bidirectional"))
      (node (ref "U6") (pin "6") (pinfunction "NO2_6") (pintype "bidirectional"))
    )
    (net (code "50") (name "unconnected-(SW1-Pad1)") (class "Default")
      (node (ref "SW1") (pin "1") (pinfunction "1_1") (pintype "bidirectional"))
    )
    (net (code "51") (name "unconnected-(SW1-Pad2)") (class "Default")
      (node (ref "SW1") (pin "2") (pinfunction "2_2") (pintype "bidirectional"))
    )
    (net (code "52") (name "unconnected-(SW1-Pad3)") (class "Default")
      (node (ref "SW1") (pin "3") (pinfunction "3_3") (pintype "bidirectional"))
    )
    (net (code "53") (name "unconnected-(SW3-Pad1)") (class "Default")
      (node (ref "SW3") (pin "1") (pinfunction "1_1") (pintype "bidirectional"))
    )
    (net (code "54") (name "unconnected-(SW3-Pad2)") (class "Default")
      (node (ref "SW3") (pin "2") (pinfunction "2_2") (pintype "bidirectional"))
    )
    (net (code "55") (name "unconnected-(SW3-Pad3)") (class "Default")
      (node (ref "SW3") (pin "3") (pinfunction "3_3") (pintype "bidirectional"))
    )
    (net (code "56") (name "unconnected-(U3-NC-Pad3)") (class "Default")
      (node (ref "U3") (pin "3") (pinfunction "NC_3") (pintype "bidirectional"))
    )
    (net (code "57") (name "unconnected-(U3-NC-Pad18)") (class "Default")
      (node (ref "U3") (pin "18") (pinfunction "NC_18") (pintype "bidirectional"))
    )
    (net (code "58") (name "unconnected-(U5-NO3-Pad10)") (class "Default")
      (node (ref "U5") (pin "10") (pinfunction "NO3_10") (pintype "bidirectional"))
    )
    (net (code "59") (name "unconnected-(U5-NO4-Pad13)") (class "Default")
      (node (ref "U5") (pin "13") (pinfunction "NO4_13") (pintype "bidirectional"))
    )
    (net (code "60") (name "unconnected-(U6-NO3-Pad10)") (class "Default")
      (node (ref "U6") (pin "10") (pinfunction "NO3_10") (pintype "bidirectional"))
    )
    (net (code "61") (name "unconnected-(U6-NO4-Pad13)") (class "Default")
      (node (ref "U6") (pin "13") (pinfunction "NO4_13") (pintype "bidirectional"))
    )
  )
)
